# power_sub_module.net
KiCad netlist of a schematic drawn in EAGLE
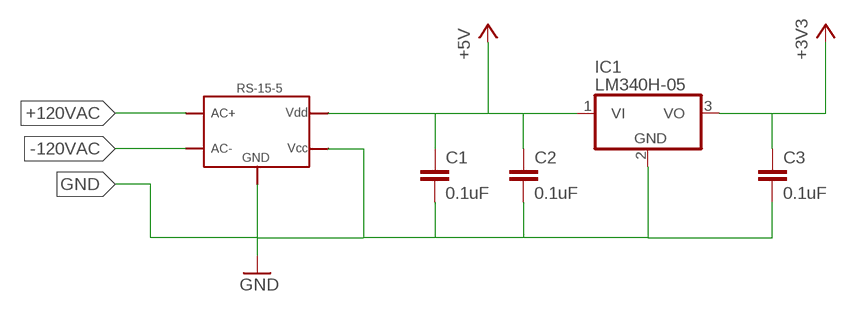
[diagram p0: schematic, sheet 1]

(export (version "E")
  (design (tool "Eeschema 10.0.6"))
  (components
    (comp (ref "C1")
      (value "0.1uF")
      (footprint "eagle-import:C025-024X044")
      (libsource (lib "eagle-import") (part "C-EU025-024X044"))
    )
    (comp (ref "C2")
      (value "0.1uF")
      (footprint "eagle-import:C025-024X044")
      (libsource (lib "eagle-import") (part "C-EU025-024X044"))
    )
    (comp (ref "C3")
      (value "0.1uF")
      (footprint "eagle-import:C025-024X044")
      (libsource (lib "eagle-import") (part "C-EU025-024X044"))
    )
    (comp (ref "IC1")
      (value "LM340H-05")
      (footprint "eagle-import:TO220H")
      (libsource (lib "eagle-import") (part "LM340?-H05"))
    )
    (comp (ref "U$1")
      (value "MOTOR")
      (footprint "eagle-import:MOTOR")
      (libsource (lib "eagle-import") (part "MOTOR"))
    )
  )
  (nets
    (net (code "1") (name "+3V3") (class "Default")
      (node (ref "C3") (pin "1") (pinfunction "1_1") (pintype "passive"))
      (node (ref "IC1") (pin "3") (pinfunction "VO_3") (pintype "passive"))
    )
    (net (code "2") (name "+5V") (class "Default")
      (node (ref "C1") (pin "1") (pinfunction "1_1") (pintype "passive"))
      (node (ref "C2") (pin "1") (pinfunction "1_1") (pintype "passive"))
      (node (ref "IC1") (pin "1") (pinfunction "VI_1") (pintype "input"))
    )
    (net (code "5") (name "GND") (class "Default")
      (node (ref "C1") (pin "2") (pinfunction "2_2") (pintype "passive"))
      (node (ref "C2") (pin "2") (pinfunction "2_2") (pintype "passive"))
      (node (ref "C3") (pin "2") (pinfunction "2_2") (pintype "passive"))
      (node (ref "IC1") (pin "2") (pinfunction "GND_2") (pintype "passive"))
    )
  )
)
